# BPMLabTXDriver.net
KiCad netlist of a schematic drawn in EAGLE
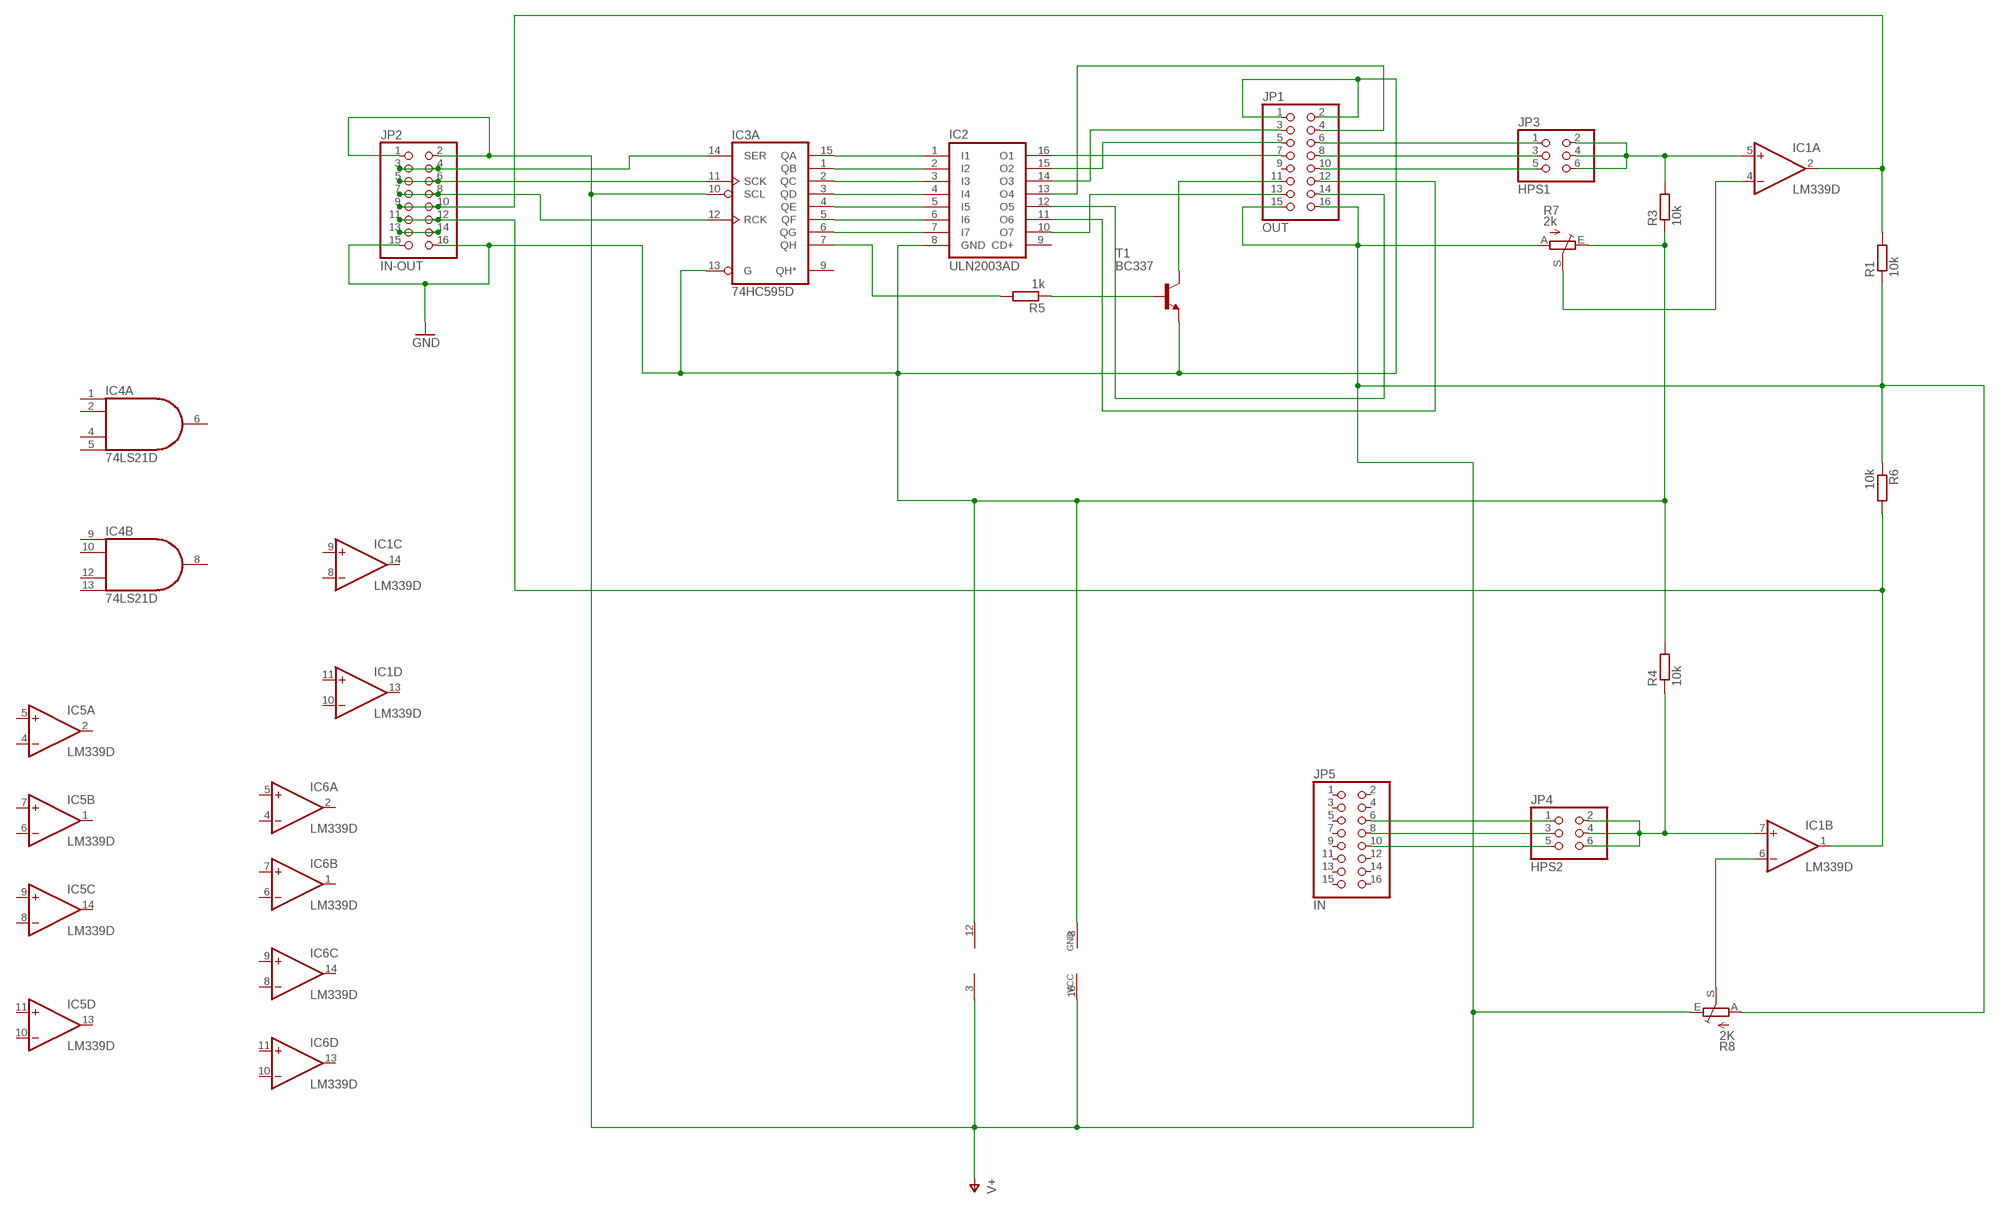
[diagram p0: schematic, sheet 1]

(export (version "E")
  (design (tool "Eeschema 10.0.6"))
  (components
    (comp (ref "IC1")
      (value "LM339D")
      (footprint "eagle-import:SO14")
      (libsource (lib "eagle-import") (part "LM339D"))
    )
    (comp (ref "IC2")
      (value "ULN2003AD")
      (footprint "eagle-import:SO16")
      (libsource (lib "eagle-import") (part "ULN2003AD"))
    )
    (comp (ref "IC3")
      (value "74HC595D")
      (footprint "eagle-import:SO16")
      (libsource (lib "eagle-import") (part "74595DHC"))
    )
    (comp (ref "IC4")
      (value "74LS21D")
      (footprint "eagle-import:SO14")
      (libsource (lib "eagle-import") (part "7421DLS"))
    )
    (comp (ref "IC5")
      (value "LM339D")
      (footprint "eagle-import:SO14")
      (libsource (lib "eagle-import") (part "LM339D"))
    )
    (comp (ref "IC6")
      (value "LM339D")
      (footprint "eagle-import:SO14")
      (libsource (lib "eagle-import") (part "LM339D"))
    )
    (comp (ref "JP1")
      (value "OUT")
      (footprint "eagle-import:2X08")
      (libsource (lib "eagle-import") (part "PINHD-2X8"))
    )
    (comp (ref "JP2")
      (value "IN-OUT")
      (footprint "eagle-import:2X08")
      (libsource (lib "eagle-import") (part "PINHD-2X8"))
    )
    (comp (ref "JP3")
      (value "HPS1")
      (footprint "eagle-import:2X03")
      (libsource (lib "eagle-import") (part "PINHD-2X3"))
    )
    (comp (ref "JP4")
      (value "HPS2")
      (footprint "eagle-import:2X03")
      (libsource (lib "eagle-import") (part "PINHD-2X3"))
    )
    (comp (ref "JP5")
      (value "IN")
      (footprint "eagle-import:2X08")
      (libsource (lib "eagle-import") (part "PINHD-2X8"))
    )
    (comp (ref "R1")
      (value "10k")
      (footprint "eagle-import:0207_10")
      (libsource (lib "eagle-import") (part "R-EU_0207/10"))
    )
    (comp (ref "R3")
      (value "10k")
      (footprint "eagle-import:0207_10")
      (libsource (lib "eagle-import") (part "R-EU_0207/10"))
    )
    (comp (ref "R4")
      (value "10k")
      (footprint "eagle-import:0207_10")
      (libsource (lib "eagle-import") (part "R-EU_0207/10"))
    )
    (comp (ref "R5")
      (value "1k")
      (footprint "eagle-import:0207_10")
      (libsource (lib "eagle-import") (part "R-EU_0207/10"))
    )
    (comp (ref "R6")
      (value "10k")
      (footprint "eagle-import:0207_10")
      (libsource (lib "eagle-import") (part "R-EU_0207/10"))
    )
    (comp (ref "R7")
      (value "2k")
      (footprint "eagle-import:RS3")
      (libsource (lib "eagle-import") (part "TRIM_EU-RS3"))
    )
    (comp (ref "R8")
      (value "2K")
      (footprint "eagle-import:RS3")
      (libsource (lib "eagle-import") (part "TRIM_EU-RS3"))
    )
    (comp (ref "T1")
      (value "BC337")
      (footprint "eagle-import:TO92-CBE")
      (libsource (lib "eagle-import") (part "-NPN-TO92-CBEBC337-16"))
    )
  )
  (nets
    (net (code "1") (name "GND") (class "Default")
      (node (ref "IC1") (pin "12") (pinfunction "GND_12") (pintype "power_in"))
      (node (ref "IC2") (pin "8") (pinfunction "GND_8") (pintype "power_in"))
      (node (ref "IC3") (pin "13") (pinfunction "G_13") (pintype "input"))
      (node (ref "IC3") (pin "8") (pinfunction "GND_8") (pintype "power_in"))
      (node (ref "JP1") (pin "1") (pinfunction "1_1") (pintype "passive"))
      (node (ref "JP1") (pin "2") (pinfunction "2_2") (pintype "passive"))
      (node (ref "JP2") (pin "15") (pinfunction "15_15") (pintype "passive"))
      (node (ref "JP2") (pin "16") (pinfunction "16_16") (pintype "passive"))
      (node (ref "R3") (pin "1") (pinfunction "1_1") (pintype "passive"))
      (node (ref "R4") (pin "2") (pinfunction "2_2") (pintype "passive"))
      (node (ref "R7") (pin "E") (pinfunction "E_E") (pintype "passive"))
      (node (ref "T1") (pin "E") (pinfunction "E_E") (pintype "passive"))
    )
    (net (code "2") (name "Net-(IC1A-+IN)") (class "Default")
      (node (ref "IC1") (pin "5") (pinfunction "+IN_5") (pintype "input"))
      (node (ref "JP3") (pin "2") (pinfunction "2_2") (pintype "passive"))
      (node (ref "JP3") (pin "4") (pinfunction "4_4") (pintype "passive"))
      (node (ref "JP3") (pin "6") (pinfunction "6_6") (pintype "passive"))
      (node (ref "R3") (pin "2") (pinfunction "2_2") (pintype "passive"))
    )
    (net (code "3") (name "Net-(IC1A--IN)") (class "Default")
      (node (ref "IC1") (pin "4") (pinfunction "-IN_4") (pintype "input"))
      (node (ref "R7") (pin "S") (pinfunction "S_S") (pintype "passive"))
    )
    (net (code "4") (name "Net-(IC1A-OUT)") (class "Default")
      (node (ref "IC1") (pin "2") (pinfunction "OUT_2") (pintype "open_collector"))
      (node (ref "JP2") (pin "10") (pinfunction "10_10") (pintype "passive"))
      (node (ref "JP2") (pin "9") (pinfunction "9_9") (pintype "passive"))
      (node (ref "R1") (pin "2") (pinfunction "2_2") (pintype "passive"))
    )
    (net (code "5") (name "Net-(IC1B-+IN)") (class "Default")
      (node (ref "IC1") (pin "7") (pinfunction "+IN_7") (pintype "input"))
      (node (ref "JP4") (pin "2") (pinfunction "2_2") (pintype "passive"))
      (node (ref "JP4") (pin "4") (pinfunction "4_4") (pintype "passive"))
      (node (ref "JP4") (pin "6") (pinfunction "6_6") (pintype "passive"))
      (node (ref "R4") (pin "1") (pinfunction "1_1") (pintype "passive"))
    )
    (net (code "6") (name "Net-(IC1B--IN)") (class "Default")
      (node (ref "IC1") (pin "6") (pinfunction "-IN_6") (pintype "input"))
      (node (ref "R8") (pin "S") (pinfunction "S_S") (pintype "passive"))
    )
    (net (code "7") (name "Net-(IC1B-OUT)") (class "Default")
      (node (ref "IC1") (pin "1") (pinfunction "OUT_1") (pintype "open_collector"))
      (node (ref "JP2") (pin "11") (pinfunction "11_11") (pintype "passive"))
      (node (ref "JP2") (pin "12") (pinfunction "12_12") (pintype "passive"))
      (node (ref "R6") (pin "2") (pinfunction "2_2") (pintype "passive"))
    )
    (net (code "8") (name "Net-(IC2-I1)") (class "Default")
      (node (ref "IC2") (pin "1") (pinfunction "I1_1") (pintype "input"))
      (node (ref "IC3") (pin "15") (pinfunction "QA_15") (pintype "tri_state"))
    )
    (net (code "9") (name "Net-(IC2-I2)") (class "Default")
      (node (ref "IC2") (pin "2") (pinfunction "I2_2") (pintype "input"))
      (node (ref "IC3") (pin "1") (pinfunction "QB_1") (pintype "tri_state"))
    )
    (net (code "10") (name "Net-(IC2-I3)") (class "Default")
      (node (ref "IC2") (pin "3") (pinfunction "I3_3") (pintype "input"))
      (node (ref "IC3") (pin "2") (pinfunction "QC_2") (pintype "tri_state"))
    )
    (net (code "11") (name "Net-(IC2-I4)") (class "Default")
      (node (ref "IC2") (pin "4") (pinfunction "I4_4") (pintype "input"))
      (node (ref "IC3") (pin "3") (pinfunction "QD_3") (pintype "tri_state"))
    )
    (net (code "12") (name "Net-(IC2-I5)") (class "Default")
      (node (ref "IC2") (pin "5") (pinfunction "I5_5") (pintype "input"))
      (node (ref "IC3") (pin "4") (pinfunction "QE_4") (pintype "tri_state"))
    )
    (net (code "13") (name "Net-(IC2-I6)") (class "Default")
      (node (ref "IC2") (pin "6") (pinfunction "I6_6") (pintype "input"))
      (node (ref "IC3") (pin "5") (pinfunction "QF_5") (pintype "tri_state"))
    )
    (net (code "14") (name "Net-(IC2-I7)") (class "Default")
      (node (ref "IC2") (pin "7") (pinfunction "I7_7") (pintype "input"))
      (node (ref "IC3") (pin "6") (pinfunction "QG_6") (pintype "tri_state"))
    )
    (net (code "15") (name "Net-(IC2-O1)") (class "Default")
      (node (ref "IC2") (pin "16") (pinfunction "O1_16") (pintype "open_collector"))
      (node (ref "JP1") (pin "7") (pinfunction "7_7") (pintype "passive"))
    )
    (net (code "16") (name "Net-(IC2-O2)") (class "Default")
      (node (ref "IC2") (pin "15") (pinfunction "O2_15") (pintype "open_collector"))
      (node (ref "JP1") (pin "5") (pinfunction "5_5") (pintype "passive"))
    )
    (net (code "17") (name "Net-(IC2-O3)") (class "Default")
      (node (ref "IC2") (pin "14") (pinfunction "O3_14") (pintype "open_collector"))
      (node (ref "JP1") (pin "3") (pinfunction "3_3") (pintype "passive"))
    )
    (net (code "18") (name "Net-(IC2-O4)") (class "Default")
      (node (ref "IC2") (pin "13") (pinfunction "O4_13") (pintype "open_collector"))
      (node (ref "JP1") (pin "4") (pinfunction "4_4") (pintype "passive"))
    )
    (net (code "19") (name "Net-(IC2-O5)") (class "Default")
      (node (ref "IC2") (pin "12") (pinfunction "O5_12") (pintype "open_collector"))
      (node (ref "JP1") (pin "14") (pinfunction "14_14") (pintype "passive"))
    )
    (net (code "20") (name "Net-(IC2-O6)") (class "Default")
      (node (ref "IC2") (pin "11") (pinfunction "O6_11") (pintype "open_collector"))
      (node (ref "JP1") (pin "12") (pinfunction "12_12") (pintype "passive"))
    )
    (net (code "21") (name "Net-(IC2-O7)") (class "Default")
      (node (ref "IC2") (pin "10") (pinfunction "O7_10") (pintype "open_collector"))
      (node (ref "JP1") (pin "13") (pinfunction "13_13") (pintype "passive"))
    )
    (net (code "22") (name "Net-(IC3A-QH)") (class "Default")
      (node (ref "IC3") (pin "7") (pinfunction "QH_7") (pintype "tri_state"))
      (node (ref "R5") (pin "2") (pinfunction "2_2") (pintype "passive"))
    )
    (net (code "23") (name "Net-(IC3A-RCK)") (class "Default")
      (node (ref "IC3") (pin "12") (pinfunction "RCK_12") (pintype "input"))
      (node (ref "JP2") (pin "7") (pinfunction "7_7") (pintype "passive"))
      (node (ref "JP2") (pin "8") (pinfunction "8_8") (pintype "passive"))
    )
    (net (code "24") (name "Net-(IC3A-SCK)") (class "Default")
      (node (ref "IC3") (pin "11") (pinfunction "SCK_11") (pintype "input"))
      (node (ref "JP2") (pin "5") (pinfunction "5_5") (pintype "passive"))
      (node (ref "JP2") (pin "6") (pinfunction "6_6") (pintype "passive"))
    )
    (net (code "25") (name "Net-(IC3A-SER)") (class "Default")
      (node (ref "IC3") (pin "14") (pinfunction "SER_14") (pintype "input"))
      (node (ref "JP2") (pin "3") (pinfunction "3_3") (pintype "passive"))
      (node (ref "JP2") (pin "4") (pinfunction "4_4") (pintype "passive"))
    )
    (net (code "26") (name "Net-(JP1-Pad6)") (class "Default")
      (node (ref "JP1") (pin "6") (pinfunction "6_6") (pintype "passive"))
      (node (ref "JP3") (pin "1") (pinfunction "1_1") (pintype "passive"))
    )
    (net (code "27") (name "Net-(JP1-Pad8)") (class "Default")
      (node (ref "JP1") (pin "8") (pinfunction "8_8") (pintype "passive"))
      (node (ref "JP3") (pin "3") (pinfunction "3_3") (pintype "passive"))
    )
    (net (code "28") (name "Net-(JP1-Pad10)") (class "Default")
      (node (ref "JP1") (pin "10") (pinfunction "10_10") (pintype "passive"))
      (node (ref "JP3") (pin "5") (pinfunction "5_5") (pintype "passive"))
    )
    (net (code "29") (name "Net-(JP1-Pad11)") (class "Default")
      (node (ref "JP1") (pin "11") (pinfunction "11_11") (pintype "passive"))
      (node (ref "T1") (pin "C") (pinfunction "C_C") (pintype "passive"))
    )
    (net (code "30") (name "Net-(JP2-Pad13)") (class "Default")
      (node (ref "JP2") (pin "13") (pinfunction "13_13") (pintype "passive"))
      (node (ref "JP2") (pin "14") (pinfunction "14_14") (pintype "passive"))
    )
    (net (code "31") (name "Net-(JP4-Pad1)") (class "Default")
      (node (ref "JP4") (pin "1") (pinfunction "1_1") (pintype "passive"))
      (node (ref "JP5") (pin "6") (pinfunction "6_6") (pintype "passive"))
    )
    (net (code "32") (name "Net-(JP4-Pad3)") (class "Default")
      (node (ref "JP4") (pin "3") (pinfunction "3_3") (pintype "passive"))
      (node (ref "JP5") (pin "8") (pinfunction "8_8") (pintype "passive"))
    )
    (net (code "33") (name "Net-(JP4-Pad5)") (class "Default")
      (node (ref "JP4") (pin "5") (pinfunction "5_5") (pintype "passive"))
      (node (ref "JP5") (pin "10") (pinfunction "10_10") (pintype "passive"))
    )
    (net (code "34") (name "Net-(R5-Pad1)") (class "Default")
      (node (ref "R5") (pin "1") (pinfunction "1_1") (pintype "passive"))
      (node (ref "T1") (pin "B") (pinfunction "B_B") (pintype "passive"))
    )
    (net (code "35") (name "V+") (class "Default")
      (node (ref "IC1") (pin "3") (pinfunction "V+_3") (pintype "power_in"))
      (node (ref "IC3") (pin "10") (pinfunction "SCL_10") (pintype "input"))
      (node (ref "IC3") (pin "16") (pinfunction "VCC_16") (pintype "power_in"))
      (node (ref "JP1") (pin "15") (pinfunction "15_15") (pintype "passive"))
      (node (ref "JP1") (pin "16") (pinfunction "16_16") (pintype "passive"))
      (node (ref "JP2") (pin "1") (pinfunction "1_1") (pintype "passive"))
      (node (ref "JP2") (pin "2") (pinfunction "2_2") (pintype "passive"))
      (node (ref "R1") (pin "1") (pinfunction "1_1") (pintype "passive"))
      (node (ref "R6") (pin "1") (pinfunction "1_1") (pintype "passive"))
      (node (ref "R7") (pin "A") (pinfunction "A_A") (pintype "passive"))
      (node (ref "R8") (pin "A") (pinfunction "A_A") (pintype "passive"))
      (node (ref "R8") (pin "E") (pinfunction "E_E") (pintype "passive"))
    )
    (net (code "36") (name "unconnected-(IC1C-+IN-Pad9)") (class "Default")
      (node (ref "IC1") (pin "9") (pinfunction "+IN_9") (pintype "input"))
    )
    (net (code "37") (name "unconnected-(IC1C--IN-Pad8)") (class "Default")
      (node (ref "IC1") (pin "8") (pinfunction "-IN_8") (pintype "input"))
    )
    (net (code "38") (name "unconnected-(IC1C-OUT-Pad14)") (class "Default")
      (node (ref "IC1") (pin "14") (pinfunction "OUT_14") (pintype "open_collector"))
    )
    (net (code "39") (name "unconnected-(IC1D-+IN-Pad11)") (class "Default")
      (node (ref "IC1") (pin "11") (pinfunction "+IN_11") (pintype "input"))
    )
    (net (code "40") (name "unconnected-(IC1D--IN-Pad10)") (class "Default")
      (node (ref "IC1") (pin "10") (pinfunction "-IN_10") (pintype "input"))
    )
    (net (code "41") (name "unconnected-(IC1D-OUT-Pad13)") (class "Default")
      (node (ref "IC1") (pin "13") (pinfunction "OUT_13") (pintype "open_collector"))
    )
    (net (code "42") (name "unconnected-(IC2-CD+-Pad9)") (class "Default")
      (node (ref "IC2") (pin "9") (pinfunction "CD+_9") (pintype "passive"))
    )
    (net (code "43") (name "unconnected-(IC3A-QH*-Pad9)") (class "Default")
      (node (ref "IC3") (pin "9") (pinfunction "QH*_9") (pintype "tri_state"))
    )
    (net (code "44") (name "unconnected-(IC4A-I0-Pad1)") (class "Default")
      (node (ref "IC4") (pin "1") (pinfunction "I0_1") (pintype "input"))
    )
    (net (code "45") (name "unconnected-(IC4A-I1-Pad2)") (class "Default")
      (node (ref "IC4") (pin "2") (pinfunction "I1_2") (pintype "input"))
    )
    (net (code "46") (name "unconnected-(IC4A-I2-Pad4)") (class "Default")
      (node (ref "IC4") (pin "4") (pinfunction "I2_4") (pintype "input"))
    )
    (net (code "47") (name "unconnected-(IC4A-I3-Pad5)") (class "Default")
      (node (ref "IC4") (pin "5") (pinfunction "I3_5") (pintype "input"))
    )
    (net (code "48") (name "unconnected-(IC4A-O-Pad6)") (class "Default")
      (node (ref "IC4") (pin "6") (pinfunction "O_6") (pintype "output"))
    )
    (net (code "49") (name "unconnected-(IC4B-I0-Pad9)") (class "Default")
      (node (ref "IC4") (pin "9") (pinfunction "I0_9") (pintype "input"))
    )
    (net (code "50") (name "unconnected-(IC4B-I1-Pad10)") (class "Default")
      (node (ref "IC4") (pin "10") (pinfunction "I1_10") (pintype "input"))
    )
    (net (code "51") (name "unconnected-(IC4B-I2-Pad12)") (class "Default")
      (node (ref "IC4") (pin "12") (pinfunction "I2_12") (pintype "input"))
    )
    (net (code "52") (name "unconnected-(IC4B-I3-Pad13)") (class "Default")
      (node (ref "IC4") (pin "13") (pinfunction "I3_13") (pintype "input"))
    )
    (net (code "53") (name "unconnected-(IC4B-O-Pad8)") (class "Default")
      (node (ref "IC4") (pin "8") (pinfunction "O_8") (pintype "output"))
    )
    (net (code "54") (name "unconnected-(IC5A-+IN-Pad5)") (class "Default")
      (node (ref "IC5") (pin "5") (pinfunction "+IN_5") (pintype "input"))
    )
    (net (code "55") (name "unconnected-(IC5A--IN-Pad4)") (class "Default")
      (node (ref "IC5") (pin "4") (pinfunction "-IN_4") (pintype "input"))
    )
    (net (code "56") (name "unconnected-(IC5A-OUT-Pad2)") (class "Default")
      (node (ref "IC5") (pin "2") (pinfunction "OUT_2") (pintype "open_collector"))
    )
    (net (code "57") (name "unconnected-(IC5B-+IN-Pad7)") (class "Default")
      (node (ref "IC5") (pin "7") (pinfunction "+IN_7") (pintype "input"))
    )
    (net (code "58") (name "unconnected-(IC5B--IN-Pad6)") (class "Default")
      (node (ref "IC5") (pin "6") (pinfunction "-IN_6") (pintype "input"))
    )
    (net (code "59") (name "unconnected-(IC5B-OUT-Pad1)") (class "Default")
      (node (ref "IC5") (pin "1") (pinfunction "OUT_1") (pintype "open_collector"))
    )
    (net (code "60") (name "unconnected-(IC5C-+IN-Pad9)") (class "Default")
      (node (ref "IC5") (pin "9") (pinfunction "+IN_9") (pintype "input"))
    )
    (net (code "61") (name "unconnected-(IC5C--IN-Pad8)") (class "Default")
      (node (ref "IC5") (pin "8") (pinfunction "-IN_8") (pintype "input"))
    )
    (net (code "62") (name "unconnected-(IC5C-OUT-Pad14)") (class "Default")
      (node (ref "IC5") (pin "14") (pinfunction "OUT_14") (pintype "open_collector"))
    )
    (net (code "63") (name "unconnected-(IC5D-+IN-Pad11)") (class "Default")
      (node (ref "IC5") (pin "11") (pinfunction "+IN_11") (pintype "input"))
    )
    (net (code "64") (name "unconnected-(IC5D--IN-Pad10)") (class "Default")
      (node (ref "IC5") (pin "10") (pinfunction "-IN_10") (pintype "input"))
    )
    (net (code "65") (name "unconnected-(IC5D-OUT-Pad13)") (class "Default")
      (node (ref "IC5") (pin "13") (pinfunction "OUT_13") (pintype "open_collector"))
    )
    (net (code "66") (name "unconnected-(IC6A-+IN-Pad5)") (class "Default")
      (node (ref "IC6") (pin "5") (pinfunction "+IN_5") (pintype "input"))
    )
    (net (code "67") (name "unconnected-(IC6A--IN-Pad4)") (class "Default")
      (node (ref "IC6") (pin "4") (pinfunction "-IN_4") (pintype "input"))
    )
    (net (code "68") (name "unconnected-(IC6A-OUT-Pad2)") (class "Default")
      (node (ref "IC6") (pin "2") (pinfunction "OUT_2") (pintype "open_collector"))
    )
    (net (code "69") (name "unconnected-(IC6B-+IN-Pad7)") (class "Default")
      (node (ref "IC6") (pin "7") (pinfunction "+IN_7") (pintype "input"))
    )
    (net (code "70") (name "unconnected-(IC6B--IN-Pad6)") (class "Default")
      (node (ref "IC6") (pin "6") (pinfunction "-IN_6") (pintype "input"))
    )
    (net (code "71") (name "unconnected-(IC6B-OUT-Pad1)") (class "Default")
      (node (ref "IC6") (pin "1") (pinfunction "OUT_1") (pintype "open_collector"))
    )
    (net (code "72") (name "unconnected-(IC6C-+IN-Pad9)") (class "Default")
      (node (ref "IC6") (pin "9") (pinfunction "+IN_9") (pintype "input"))
    )
    (net (code "73") (name "unconnected-(IC6C--IN-Pad8)") (class "Default")
      (node (ref "IC6") (pin "8") (pinfunction "-IN_8") (pintype "input"))
    )
    (net (code "74") (name "unconnected-(IC6C-OUT-Pad14)") (class "Default")
      (node (ref "IC6") (pin "14") (pinfunction "OUT_14") (pintype "open_collector"))
    )
    (net (code "75") (name "unconnected-(IC6D-+IN-Pad11)") (class "Default")
      (node (ref "IC6") (pin "11") (pinfunction "+IN_11") (pintype "input"))
    )
    (net (code "76") (name "unconnected-(IC6D--IN-Pad10)") (class "Default")
      (node (ref "IC6") (pin "10") (pinfunction "-IN_10") (pintype "input"))
    )
    (net (code "77") (name "unconnected-(IC6D-OUT-Pad13)") (class "Default")
      (node (ref "IC6") (pin "13") (pinfunction "OUT_13") (pintype "open_collector"))
    )
    (net (code "78") (name "unconnected-(JP1-Pad9)") (class "Default")
      (node (ref "JP1") (pin "9") (pinfunction "9_9") (pintype "passive"))
    )
    (net (code "79") (name "unconnected-(JP5-Pad1)") (class "Default")
      (node (ref "JP5") (pin "1") (pinfunction "1_1") (pintype "passive"))
    )
    (net (code "80") (name "unconnected-(JP5-Pad2)") (class "Default")
      (node (ref "JP5") (pin "2") (pinfunction "2_2") (pintype "passive"))
    )
    (net (code "81") (name "unconnected-(JP5-Pad3)") (class "Default")
      (node (ref "JP5") (pin "3") (pinfunction "3_3") (pintype "passive"))
    )
    (net (code "82") (name "unconnected-(JP5-Pad4)") (class "Default")
      (node (ref "JP5") (pin "4") (pinfunction "4_4") (pintype "passive"))
    )
    (net (code "83") (name "unconnected-(JP5-Pad5)") (class "Default")
      (node (ref "JP5") (pin "5") (pinfunction "5_5") (pintype "passive"))
    )
    (net (code "84") (name "unconnected-(JP5-Pad7)") (class "Default")
      (node (ref "JP5") (pin "7") (pinfunction "7_7") (pintype "passive"))
    )
    (net (code "85") (name "unconnected-(JP5-Pad9)") (class "Default")
      (node (ref "JP5") (pin "9") (pinfunction "9_9") (pintype "passive"))
    )
    (net (code "86") (name "unconnected-(JP5-Pad11)") (class "Default")
      (node (ref "JP5") (pin "11") (pinfunction "11_11") (pintype "passive"))
    )
    (net (code "87") (name "unconnected-(JP5-Pad12)") (class "Default")
      (node (ref "JP5") (pin "12") (pinfunction "12_12") (pintype "passive"))
    )
    (net (code "88") (name "unconnected-(JP5-Pad13)") (class "Default")
      (node (ref "JP5") (pin "13") (pinfunction "13_13") (pintype "passive"))
    )
    (net (code "89") (name "unconnected-(JP5-Pad14)") (class "Default")
      (node (ref "JP5") (pin "14") (pinfunction "14_14") (pintype "passive"))
    )
    (net (code "90") (name "unconnected-(JP5-Pad15)") (class "Default")
      (node (ref "JP5") (pin "15") (pinfunction "15_15") (pintype "passive"))
    )
    (net (code "91") (name "unconnected-(JP5-Pad16)") (class "Default")
      (node (ref "JP5") (pin "16") (pinfunction "16_16") (pintype "passive"))
    )
  )
)
